# MotorConnector.net
KiCad netlist of a schematic drawn in Altium Designer
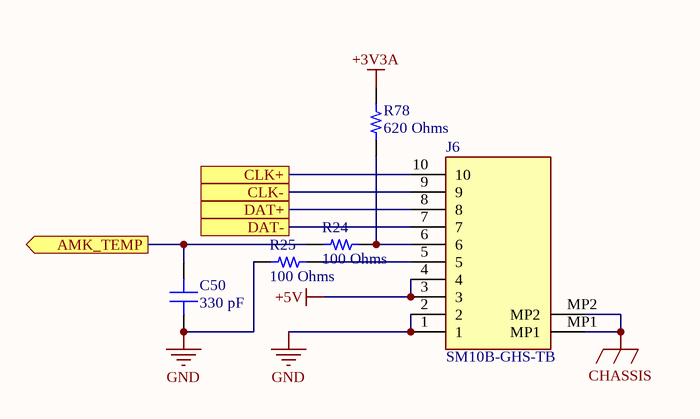
[diagram p0: MotorConnector.SchDoc]

(export (version "E")
  (design (tool "Eeschema 10.0.6"))
  (components
    (comp (ref "C50")
      (value "330 pF")
      (footprint "CAP 0402_1005")
      (description "CAP CER 330PF 100V X7R 0402")
      (fields
        (field (name "PART NUMBER") "HMK105B7331MV-F")
        (field (name "CAPACITANCE") "330 pF")
        (field (name "MANUFACTURER") "Taiyo Yuden")
      )
      (libsource (lib "Celestial Altium Library - altium_library") (part "Capacitor"))
    )
    (comp (ref "J6")
      (value "SM10B-GHS-TB")
      (footprint "PcbLib1:SM10BGHSTB")
      (description "Connector")
      (libsource (lib "*") (part "SM10B-GHS-TB"))
    )
    (comp (ref "R24")
      (value "100 Ohms")
      (footprint "RES 0402_1005")
      (description "RES 100 OHM 1% 1/16W 0402")
      (fields
        (field (name "PART NUMBER") "WR04X1000FTL")
        (field (name "MANUFACTURER") "Walsin Technology Corporation")
      )
      (libsource (lib "Celestial Altium Library - altium_library") (part "Resistor"))
    )
    (comp (ref "R25")
      (value "100 Ohms")
      (footprint "RES 0402_1005")
      (description "RES 100 OHM 1% 1/16W 0402")
      (fields
        (field (name "PART NUMBER") "WR04X1000FTL")
        (field (name "MANUFACTURER") "Walsin Technology Corporation")
      )
      (libsource (lib "Celestial Altium Library - altium_library") (part "Resistor"))
    )
    (comp (ref "R78")
      (value "620 Ohms")
      (footprint "YAGEO RES 0402_1005")
      (description "RES 620 OHM 5% 1/16W 0402")
      (fields (field (name "PART NUMBER") "RC0402JR-07620RL") (field (name "MANUFACTURER") "Yageo"))
      (libsource (lib "Celestial Altium Library - altium_library") (part "Resistor"))
    )
  )
  (nets
    (net (code "1") (name "+3V3A") (class "Default")
      (node (ref "R78") (pin "2") (pinfunction "2_2") (pintype "passive"))
    )
    (net (code "2") (name "+5V") (class "Default")
      (node (ref "J6") (pin "3") (pinfunction "3_3") (pintype "passive"))
      (node (ref "J6") (pin "4") (pinfunction "4_4") (pintype "passive"))
    )
    (net (code "3") (name "/AMK_TEMP") (class "Default")
      (node (ref "C50") (pin "2") (pinfunction "2_2") (pintype "passive"))
      (node (ref "R24") (pin "1") (pinfunction "1_1") (pintype "passive"))
    )
    (net (code "4") (name "/CLK+") (class "Default")
      (node (ref "J6") (pin "10") (pinfunction "10_10") (pintype "passive"))
    )
    (net (code "5") (name "/CLK-") (class "Default")
      (node (ref "J6") (pin "9") (pinfunction "9_9") (pintype "passive"))
    )
    (net (code "6") (name "/DAT+") (class "Default")
      (node (ref "J6") (pin "8") (pinfunction "8_8") (pintype "passive"))
    )
    (net (code "7") (name "/DAT-") (class "Default")
      (node (ref "J6") (pin "7") (pinfunction "7_7") (pintype "passive"))
    )
    (net (code "8") (name "CHASSIS") (class "Default")
      (node (ref "J6") (pin "MP1") (pinfunction "MP1_MP1") (pintype "passive"))
      (node (ref "J6") (pin "MP2") (pinfunction "MP2_MP2") (pintype "passive"))
    )
    (net (code "9") (name "GND") (class "Default")
      (node (ref "C50") (pin "1") (pinfunction "1_1") (pintype "passive"))
      (node (ref "J6") (pin "1") (pinfunction "1_1") (pintype "passive"))
      (node (ref "J6") (pin "2") (pinfunction "2_2") (pintype "passive"))
      (node (ref "R25") (pin "1") (pinfunction "1_1") (pintype "passive"))
    )
    (net (code "10") (name "Net-(J6-Pad5)") (class "Default")
      (node (ref "J6") (pin "5") (pinfunction "5_5") (pintype "passive"))
      (node (ref "R25") (pin "2") (pinfunction "2_2") (pintype "passive"))
    )
    (net (code "11") (name "Net-(J6-Pad6)") (class "Default")
      (node (ref "J6") (pin "6") (pinfunction "6_6") (pintype "passive"))
      (node (ref "R24") (pin "2") (pinfunction "2_2") (pintype "passive"))
      (node (ref "R78") (pin "1") (pinfunction "1_1") (pintype "passive"))
    )
  )
)
